# 01_MAIN.net
KiCad netlist of a schematic drawn in Altium Designer
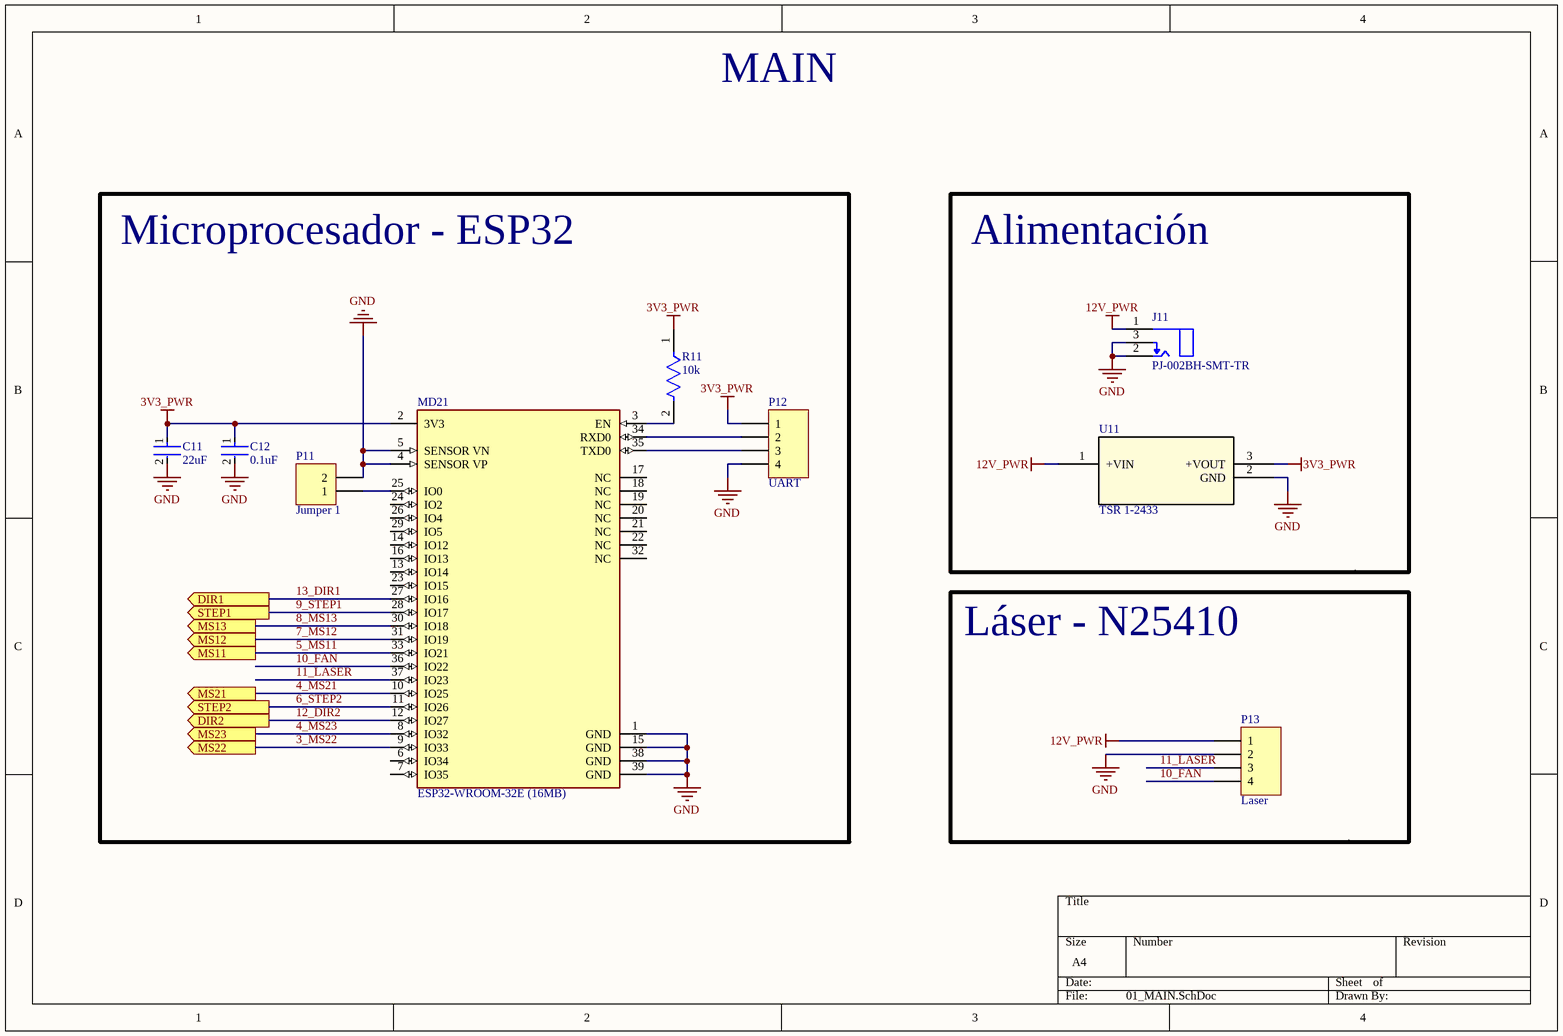
[diagram p0: 01_MAIN.SchDoc]

(export (version "E")
  (design (tool "Eeschema 10.0.6"))
  (components
    (comp (ref "C11")
      (value "22uF")
      (footprint "FP-0603-L_1_6_0_15-W_0_81-MFG")
      (description "General Purpose Ceramic Capacitor, 0603, 22uF, 20%, X5R, 15%, 10V")
      (fields (field (name "TOLERANCE") "20%") (field (name "MANUFACTURER") "Kyocera AVX"))
      (libsource (lib "Altium Content Vault") (part "b4654b650e69147ec39a6b967a45e02"))
    )
    (comp (ref "C12")
      (value "0.1uF")
      (footprint "FP-CC0603-DA-IPC_A")
      (description "CAP CER 0.1UF 50V X7R 0603")
      (fields (field (name "TOLERANCE") "5%") (field (name "MANUFACTURER") "Yageo"))
      (libsource (lib "Altium Content Vault") (part "02cd4be3c70576c341d710602a673aa"))
    )
    (comp (ref "J11")
      (value "PJ-002BH-SMT-TR")
      (footprint "FP-PJ-002BH-SMT-TR-MFG")
      (description "CONN PWR JACK 2.5X5.5MM SOLDER")
      (fields
        (field (name "MANUFACTURER") "CUI Inc")
        (field (name "OCTOPART") "https://octopart.com/pj-002bh-smt-tr-cui-25947151")
      )
      (libsource (lib "Altium Content Vault") (part "020ff674638626da6de6501228ee46e"))
    )
    (comp (ref "MD21")
      (value "ESP32-WROOM-32E (16MB)")
      (footprint "FP-ESP32-WROOM-32E_16MB-MFG")
      (description "RX TXRX MOD WIFI TRACE ANT SMD")
      (libsource (lib "Altium Content Vault") (part "77f46594ed2a4fcc7e275071e067929"))
    )
    (comp (ref "P11")
      (value "Jumper 1")
      (footprint "HDR1X2")
      (description "Header, 2-Pin")
      (fields (field (name "PUBLISHER") "Altium Limited"))
      (libsource (lib "Miscellaneous Connectors") (part "Header 2"))
    )
    (comp (ref "P12")
      (value "UART")
      (footprint "HDR1X4")
      (description "Header, 4-Pin")
      (fields (field (name "PUBLISHER") "Altium Limited"))
      (libsource (lib "Miscellaneous Connectors") (part "Header 4"))
    )
    (comp (ref "P13")
      (value "Laser")
      (footprint "HDR1X4")
      (description "Header, 4-Pin")
      (fields (field (name "PUBLISHER") "Altium Limited"))
      (libsource (lib "Miscellaneous Connectors") (part "Header 4"))
    )
    (comp (ref "R11")
      (value "10k")
      (footprint "FP-RC0603-0_55-IPC_C")
      (description "RES 10K OHM 1% 1/10W 0603")
      (fields (field (name "TOLERANCE") "1%") (field (name "MANUFACTURER") "Yageo"))
      (libsource (lib "Altium Content Vault") (part "1029c3af85768c4190bb7ad29bc67b5"))
    )
    (comp (ref "U11")
      (value "TSR 1-2433")
      (footprint "TSR1-SINGLE_TRP")
      (fields
        (field (name "MANUFACTURER") "Traco Power")
        (field (name "MANUFACTURER PART NUMBER") "TSR1-2433")
      )
      (libsource (lib "Altium Content Vault") (part "TSR 1-2433"))
    )
  )
  (nets
    (net (code "1") (name "/3_MS22") (class "Default")
      (node (ref "MD21") (pin "9") (pinfunction "IO33_9") (pintype "bidirectional"))
    )
    (net (code "2") (name "/4_MS21") (class "Default")
      (node (ref "MD21") (pin "10") (pinfunction "IO25_10") (pintype "bidirectional"))
    )
    (net (code "3") (name "/4_MS23") (class "Default")
      (node (ref "MD21") (pin "8") (pinfunction "IO32_8") (pintype "bidirectional"))
    )
    (net (code "4") (name "/5_MS11") (class "Default")
      (node (ref "MD21") (pin "33") (pinfunction "IO21_33") (pintype "bidirectional"))
    )
    (net (code "5") (name "/6_STEP2") (class "Default")
      (node (ref "MD21") (pin "11") (pinfunction "IO26_11") (pintype "bidirectional"))
    )
    (net (code "6") (name "/7_MS12") (class "Default")
      (node (ref "MD21") (pin "31") (pinfunction "IO19_31") (pintype "bidirectional"))
    )
    (net (code "7") (name "/8_MS13") (class "Default")
      (node (ref "MD21") (pin "30") (pinfunction "IO18_30") (pintype "bidirectional"))
    )
    (net (code "8") (name "/9_STEP1") (class "Default")
      (node (ref "MD21") (pin "28") (pinfunction "IO17_28") (pintype "bidirectional"))
    )
    (net (code "9") (name "/10_FAN") (class "Default")
      (node (ref "MD21") (pin "36") (pinfunction "IO22_36") (pintype "bidirectional"))
      (node (ref "P13") (pin "4") (pinfunction "4_4") (pintype "passive"))
    )
    (net (code "10") (name "/11_LASER") (class "Default")
      (node (ref "MD21") (pin "37") (pinfunction "IO23_37") (pintype "bidirectional"))
      (node (ref "P13") (pin "3") (pinfunction "3_3") (pintype "passive"))
    )
    (net (code "11") (name "/12_DIR2") (class "Default")
      (node (ref "MD21") (pin "12") (pinfunction "IO27_12") (pintype "bidirectional"))
    )
    (net (code "12") (name "/13_DIR1") (class "Default")
      (node (ref "MD21") (pin "27") (pinfunction "IO16_27") (pintype "bidirectional"))
    )
    (net (code "13") (name "3V3_PWR") (class "Default")
      (node (ref "C11") (pin "1") (pinfunction "1_1") (pintype "passive"))
      (node (ref "C12") (pin "1") (pinfunction "1_1") (pintype "passive"))
      (node (ref "MD21") (pin "2") (pinfunction "3V3_2") (pintype "power_in"))
      (node (ref "P12") (pin "1") (pinfunction "1_1") (pintype "passive"))
      (node (ref "R11") (pin "1") (pinfunction "1_1") (pintype "passive"))
      (node (ref "U11") (pin "3") (pinfunction "+VOUT_3") (pintype "power_in"))
    )
    (net (code "14") (name "12V_PWR") (class "Default")
      (node (ref "J11") (pin "1") (pinfunction "1_1") (pintype "passive"))
      (node (ref "P13") (pin "1") (pinfunction "1_1") (pintype "passive"))
      (node (ref "U11") (pin "1") (pinfunction "+VIN_1") (pintype "power_in"))
    )
    (net (code "15") (name "GND") (class "Default")
      (node (ref "C11") (pin "2") (pinfunction "2_2") (pintype "passive"))
      (node (ref "C12") (pin "2") (pinfunction "2_2") (pintype "passive"))
      (node (ref "J11") (pin "2") (pinfunction "2_2") (pintype "passive"))
      (node (ref "J11") (pin "3") (pinfunction "3_3") (pintype "passive"))
      (node (ref "MD21") (pin "1") (pinfunction "GND_1") (pintype "power_in"))
      (node (ref "MD21") (pin "15") (pinfunction "GND_15") (pintype "power_in"))
      (node (ref "MD21") (pin "38") (pinfunction "GND_38") (pintype "power_in"))
      (node (ref "MD21") (pin "39") (pinfunction "GND_39") (pintype "power_in"))
      (node (ref "MD21") (pin "4") (pinfunction "SENSOR_VP_4") (pintype "input"))
      (node (ref "MD21") (pin "5") (pinfunction "SENSOR_VN_5") (pintype "input"))
      (node (ref "P11") (pin "2") (pinfunction "2_2") (pintype "passive"))
      (node (ref "P12") (pin "4") (pinfunction "4_4") (pintype "passive"))
      (node (ref "P13") (pin "2") (pinfunction "2_2") (pintype "passive"))
      (node (ref "U11") (pin "2") (pinfunction "GND_2") (pintype "power_in"))
    )
    (net (code "16") (name "Net-(MD21-EN)") (class "Default")
      (node (ref "MD21") (pin "3") (pinfunction "EN_3") (pintype "input"))
      (node (ref "R11") (pin "2") (pinfunction "2_2") (pintype "passive"))
    )
    (net (code "17") (name "Net-(MD21-IO0)") (class "Default")
      (node (ref "MD21") (pin "25") (pinfunction "IO0_25") (pintype "bidirectional"))
      (node (ref "P11") (pin "1") (pinfunction "1_1") (pintype "passive"))
    )
    (net (code "18") (name "Net-(MD21-RXD0)") (class "Default")
      (node (ref "MD21") (pin "34") (pinfunction "RXD0_34") (pintype "bidirectional"))
      (node (ref "P12") (pin "2") (pinfunction "2_2") (pintype "passive"))
    )
    (net (code "19") (name "Net-(MD21-TXD0)") (class "Default")
      (node (ref "MD21") (pin "35") (pinfunction "TXD0_35") (pintype "bidirectional"))
      (node (ref "P12") (pin "3") (pinfunction "3_3") (pintype "passive"))
    )
    (net (code "20") (name "unconnected-(MD21-IO2-Pad24)") (class "Default")
      (node (ref "MD21") (pin "24") (pinfunction "IO2_24") (pintype "bidirectional"))
    )
    (net (code "21") (name "unconnected-(MD21-IO4-Pad26)") (class "Default")
      (node (ref "MD21") (pin "26") (pinfunction "IO4_26") (pintype "bidirectional"))
    )
    (net (code "22") (name "unconnected-(MD21-IO5-Pad29)") (class "Default")
      (node (ref "MD21") (pin "29") (pinfunction "IO5_29") (pintype "bidirectional"))
    )
    (net (code "23") (name "unconnected-(MD21-IO12-Pad14)") (class "Default")
      (node (ref "MD21") (pin "14") (pinfunction "IO12_14") (pintype "bidirectional"))
    )
    (net (code "24") (name "unconnected-(MD21-IO13-Pad16)") (class "Default")
      (node (ref "MD21") (pin "16") (pinfunction "IO13_16") (pintype "bidirectional"))
    )
    (net (code "25") (name "unconnected-(MD21-IO14-Pad13)") (class "Default")
      (node (ref "MD21") (pin "13") (pinfunction "IO14_13") (pintype "bidirectional"))
    )
    (net (code "26") (name "unconnected-(MD21-IO15-Pad23)") (class "Default")
      (node (ref "MD21") (pin "23") (pinfunction "IO15_23") (pintype "bidirectional"))
    )
    (net (code "27") (name "unconnected-(MD21-IO34-Pad6)") (class "Default")
      (node (ref "MD21") (pin "6") (pinfunction "IO34_6") (pintype "bidirectional"))
    )
    (net (code "28") (name "unconnected-(MD21-IO35-Pad7)") (class "Default")
      (node (ref "MD21") (pin "7") (pinfunction "IO35_7") (pintype "bidirectional"))
    )
    (net (code "29") (name "unconnected-(MD21-NC-Pad17)") (class "Default")
      (node (ref "MD21") (pin "17") (pinfunction "NC_17") (pintype "passive"))
    )
    (net (code "30") (name "unconnected-(MD21-NC-Pad18)") (class "Default")
      (node (ref "MD21") (pin "18") (pinfunction "NC_18") (pintype "passive"))
    )
    (net (code "31") (name "unconnected-(MD21-NC-Pad19)") (class "Default")
      (node (ref "MD21") (pin "19") (pinfunction "NC_19") (pintype "passive"))
    )
    (net (code "32") (name "unconnected-(MD21-NC-Pad20)") (class "Default")
      (node (ref "MD21") (pin "20") (pinfunction "NC_20") (pintype "passive"))
    )
    (net (code "33") (name "unconnected-(MD21-NC-Pad21)") (class "Default")
      (node (ref "MD21") (pin "21") (pinfunction "NC_21") (pintype "passive"))
    )
    (net (code "34") (name "unconnected-(MD21-NC-Pad22)") (class "Default")
      (node (ref "MD21") (pin "22") (pinfunction "NC_22") (pintype "passive"))
    )
    (net (code "35") (name "unconnected-(MD21-NC-Pad32)") (class "Default")
      (node (ref "MD21") (pin "32") (pinfunction "NC_32") (pintype "passive"))
    )
  )
)
